# microsd.net
KiCad netlist of a schematic drawn in Altium Designer
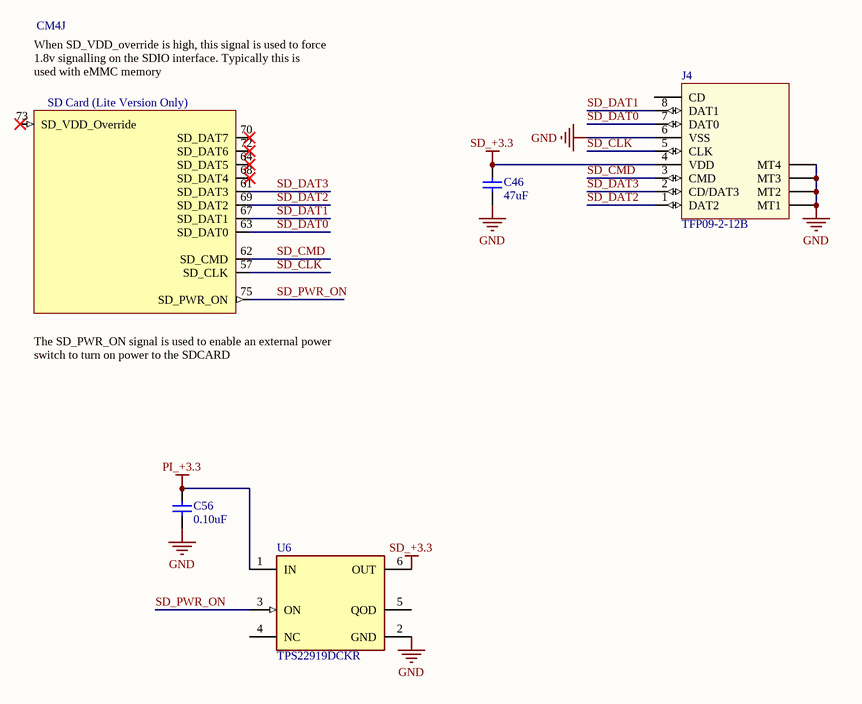
[diagram p0: microsd.SchDoc]

(export (version "E")
  (design (tool "Eeschema 10.0.6"))
  (components
    (comp (ref "C46")
      (value "47uF")
      (footprint "CAPC1608X09L")
      (description "CAP CER 47UF 6.3V X5R 0603")
      (fields
        (field (name "PARTNUMBER") "ZRB18AR60J476ME01L")
        (field (name "DIGI-KEY PART NUMBER") "490-13255-1-ND")
      )
      (libsource (lib "cap_murata") (part "CAPACITOR"))
    )
    (comp (ref "C56")
      (value "0.10uF")
      (footprint "CAPC1005X06L")
      (description "CAP CER 0.1UF 10V X5R 0402")
      (fields
        (field (name "PARTNUMBER") "GRM155R61A104KA01D")
        (field (name "DIGI-KEY PART NUMBER") "490-1318-1-ND")
      )
      (libsource (lib "cap_murata") (part "CAPACITOR"))
    )
    (comp (ref "CM4")
      (value "Raspberry Pi Compute Module 4")
      (footprint "CM4-F40C-100DS-0.4v_1.5mm_0mm")
      (description "Raspberry Pi Compute Module 4 by Amornthep Phunsin")
      (libsource (lib "CM4") (part "CM4"))
    )
    (comp (ref "J4")
      (value "TFP09-2-12B")
      (footprint "TFP09-2-12B")
      (description "Micro SD Card Connector")
      (fields (field (name "MANUFACTURER") "Unknown/Generic"))
      (libsource (lib "Blinkinlabs") (part "TFP09-2-12B"))
    )
    (comp (ref "U6")
      (value "TPS22919DCKR")
      (footprint "FP-DCK0006A-MFG")
      (description "POWER MANAGEMENT")
      (libsource (lib "Altium Content Vault") (part "7dede5ae6ec4f64f362f8612ed9bb45"))
    )
  )
  (nets
    (net (code "1") (name "/SD_CLK") (class "Default")
      (node (ref "CM4") (pin "57") (pinfunction "SD_CLK_57") (pintype "passive"))
      (node (ref "J4") (pin "5") (pinfunction "CLK_5") (pintype "bidirectional"))
    )
    (net (code "2") (name "/SD_CMD") (class "Default")
      (node (ref "CM4") (pin "62") (pinfunction "SD_CMD_62") (pintype "passive"))
      (node (ref "J4") (pin "3") (pinfunction "CMD_3") (pintype "bidirectional"))
    )
    (net (code "3") (name "/SD_DAT0") (class "Default")
      (node (ref "CM4") (pin "63") (pinfunction "SD_DAT0_63") (pintype "passive"))
      (node (ref "J4") (pin "7") (pinfunction "DAT0_7") (pintype "bidirectional"))
    )
    (net (code "4") (name "/SD_DAT1") (class "Default")
      (node (ref "CM4") (pin "67") (pinfunction "SD_DAT1_67") (pintype "passive"))
      (node (ref "J4") (pin "8") (pinfunction "DAT1_8") (pintype "bidirectional"))
    )
    (net (code "5") (name "/SD_DAT2") (class "Default")
      (node (ref "CM4") (pin "69") (pinfunction "SD_DAT2_69") (pintype "passive"))
      (node (ref "J4") (pin "1") (pinfunction "DAT2_1") (pintype "bidirectional"))
    )
    (net (code "6") (name "/SD_DAT3") (class "Default")
      (node (ref "CM4") (pin "61") (pinfunction "SD_DAT3_61") (pintype "passive"))
      (node (ref "J4") (pin "2") (pinfunction "CD/DAT3_2") (pintype "bidirectional"))
    )
    (net (code "7") (name "/SD_PWR_ON") (class "Default")
      (node (ref "CM4") (pin "75") (pinfunction "SD_PWR_ON_75") (pintype "output"))
      (node (ref "U6") (pin "3") (pinfunction "ON_3") (pintype "input"))
    )
    (net (code "8") (name "GND") (class "Default")
      (node (ref "C46") (pin "2") (pinfunction "2_2") (pintype "passive"))
      (node (ref "C56") (pin "1") (pinfunction "1_1") (pintype "passive"))
      (node (ref "J4") (pin "6") (pinfunction "VSS_6") (pintype "power_in"))
      (node (ref "J4") (pin "MT1") (pinfunction "MT1_MT1") (pintype "passive"))
      (node (ref "J4") (pin "MT2") (pinfunction "MT2_MT2") (pintype "passive"))
      (node (ref "J4") (pin "MT3") (pinfunction "MT3_MT3") (pintype "passive"))
      (node (ref "J4") (pin "MT4") (pinfunction "MT4_MT4") (pintype "passive"))
      (node (ref "U6") (pin "2") (pinfunction "GND_2") (pintype "power_in"))
    )
    (net (code "9") (name "PI_+3.3") (class "Default")
      (node (ref "C56") (pin "2") (pinfunction "2_2") (pintype "passive"))
      (node (ref "U6") (pin "1") (pinfunction "IN_1") (pintype "power_in"))
    )
    (net (code "10") (name "SD_+3.3") (class "Default")
      (node (ref "C46") (pin "1") (pinfunction "1_1") (pintype "passive"))
      (node (ref "J4") (pin "4") (pinfunction "VDD_4") (pintype "power_in"))
      (node (ref "U6") (pin "6") (pinfunction "OUT_6") (pintype "power_in"))
    )
    (net (code "11") (name "unconnected-(CM4J-SD_DAT4-Pad68)") (class "Default")
      (node (ref "CM4") (pin "68") (pinfunction "SD_DAT4_68") (pintype "passive+no_connect"))
    )
    (net (code "12") (name "unconnected-(CM4J-SD_DAT5-Pad64)") (class "Default")
      (node (ref "CM4") (pin "64") (pinfunction "SD_DAT5_64") (pintype "passive+no_connect"))
    )
    (net (code "13") (name "unconnected-(CM4J-SD_DAT6-Pad72)") (class "Default")
      (node (ref "CM4") (pin "72") (pinfunction "SD_DAT6_72") (pintype "passive+no_connect"))
    )
    (net (code "14") (name "unconnected-(CM4J-SD_DAT7-Pad70)") (class "Default")
      (node (ref "CM4") (pin "70") (pinfunction "SD_DAT7_70") (pintype "passive+no_connect"))
    )
    (net (code "15") (name "unconnected-(CM4J-SD_VDD_Override-Pad73)") (class "Default")
      (node (ref "CM4") (pin "73") (pinfunction "SD_VDD_Override_73") (pintype "input+no_connect"))
    )
    (net (code "16") (name "unconnected-(J4-PadCD)") (class "Default")
      (node (ref "J4") (pin "CD") (pinfunction "CD_CD") (pintype "passive"))
    )
    (net (code "17") (name "unconnected-(U6-NC-Pad4)") (class "Default")
      (node (ref "U6") (pin "4") (pinfunction "NC_4") (pintype "passive"))
    )
    (net (code "18") (name "unconnected-(U6-QOD-Pad5)") (class "Default")
      (node (ref "U6") (pin "5") (pinfunction "QOD_5") (pintype "passive"))
    )
  )
)
